# Sheet1-control.net
KiCad netlist of a schematic drawn in Altium Designer
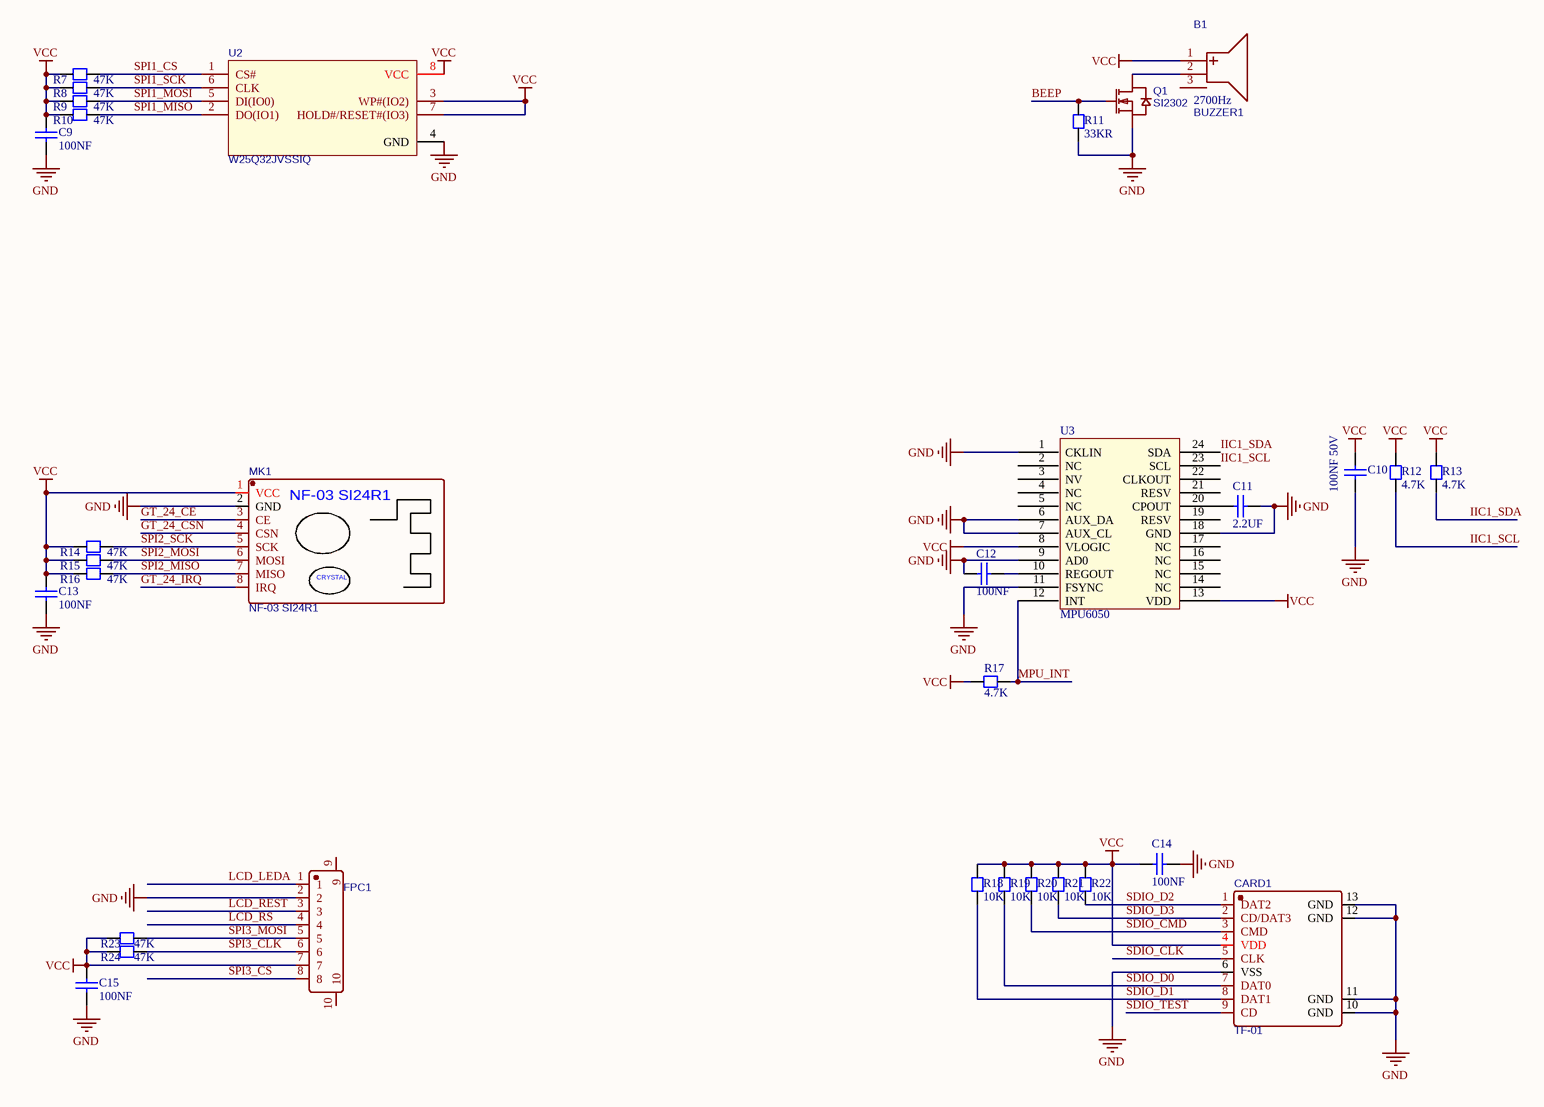
[diagram p0: Sheet1-control.SchDoc]

(export (version "E")
  (design (tool "Eeschema 10.0.6"))
  (components
    (comp (ref "B1")
      (value "BUZZER1")
      (footprint "BUZ-SMD_GSC7525RA")
      (description "2700Hz")
      (fields
        (field (name "MANUFACTURER") "INGHAi(赢海)")
        (field (name "MANUFACTURER PART") "GSC7525RA-16R2700")
        (field (name "CONTRIBUTOR") "LCSC")
      )
      (libsource (lib "base") (part "BUZZER1"))
    )
    (comp (ref "C9")
      (value "100NF")
      (footprint "CC1608-0603")
      (description "0603封装的电容")
      (fields (field (name "PUBLISHER") "Altium Limited"))
      (libsource (lib "base") (part "Cap Chip 0603"))
    )
    (comp (ref "C10")
      (value "100NF 50V")
      (footprint "CC1608-0603")
      (description "0603封装的电容")
      (fields (field (name "PUBLISHER") "Altium Limited"))
      (libsource (lib "base") (part "Cap Chip 0603"))
    )
    (comp (ref "C11")
      (value "2.2UF")
      (footprint "CC1608-0603")
      (description "0603封装的电容")
      (fields (field (name "PUBLISHER") "Altium Limited"))
      (libsource (lib "base") (part "Cap Chip 0603"))
    )
    (comp (ref "C12")
      (value "100NF")
      (footprint "CC1608-0603")
      (description "0603封装的电容")
      (fields (field (name "PUBLISHER") "Altium Limited"))
      (libsource (lib "base") (part "Cap Chip 0603"))
    )
    (comp (ref "C13")
      (value "100NF")
      (footprint "CC1608-0603")
      (description "0603封装的电容")
      (fields (field (name "PUBLISHER") "Altium Limited"))
      (libsource (lib "base") (part "Cap Chip 0603"))
    )
    (comp (ref "C14")
      (value "100NF")
      (footprint "CC1608-0603")
      (description "0603封装的电容")
      (fields (field (name "PUBLISHER") "Altium Limited"))
      (libsource (lib "base") (part "Cap Chip 0603"))
    )
    (comp (ref "C15")
      (value "100NF")
      (footprint "CC1608-0603")
      (description "0603封装的电容")
      (fields (field (name "PUBLISHER") "Altium Limited"))
      (libsource (lib "base") (part "Cap Chip 0603"))
    )
    (comp (ref "CARD1")
      (value "TF-01")
      (footprint "TF-SMD_TF-15-15")
      (fields (field (name "MANUFACTURER") "Yuandi(元迪)") (field (name "CONTRIBUTOR") "LCSC"))
      (libsource (lib "Connectors") (part "TF-01"))
    )
    (comp (ref "FPC1")
      (value "FFC 05 8P")
      (footprint "FFC-SMD_8P-P0.50")
      (fields
        (field (name "MANUFACTURER") "TXGA(特思嘉)")
        (field (name "MANUFACTURER PART") "FFC05001-08SBB124W5M-H")
        (field (name "CONTRIBUTOR") "LCSC")
      )
      (libsource (lib "Connectors") (part "FFC 05 8P"))
    )
    (comp (ref "MK1")
      (value "NF-03 SI24R1")
      (footprint "NF-03 SI24R1")
      (fields (field (name "MANUFACTURER") "Ashining(泽耀科技)") (field (name "MANUFACTURER PART") "AS01-ML01S"))
      (libsource (lib "sensor") (part "NF-03 SI24R1"))
    )
    (comp (ref "Q1")
      (value "SI2302")
      (footprint "SOT-23")
      (fields
        (field (name "MANUFACTURER") "TWGMC(台湾迪嘉)")
        (field (name "MANUFACTURER PART") "SI2306")
        (field (name "CONTRIBUTOR") "LCSC")
      )
      (libsource (lib "transistor") (part "SI2302"))
    )
    (comp (ref "R7")
      (value "47K")
      (footprint "CR1608-0603")
      (description "贴片电阻")
      (libsource (lib "tianxiaohua_Schlib") (part "Chip resistor"))
    )
    (comp (ref "R8")
      (value "47K")
      (footprint "CR1608-0603")
      (description "贴片电阻")
      (libsource (lib "tianxiaohua_Schlib") (part "Chip resistor"))
    )
    (comp (ref "R9")
      (value "47K")
      (footprint "CR1608-0603")
      (description "贴片电阻")
      (libsource (lib "tianxiaohua_Schlib") (part "Chip resistor"))
    )
    (comp (ref "R10")
      (value "47K")
      (footprint "CR1608-0603")
      (description "贴片电阻")
      (libsource (lib "tianxiaohua_Schlib") (part "Chip resistor"))
    )
    (comp (ref "R11")
      (value "33KR")
      (footprint "CR1608-0603")
      (description "贴片电阻")
      (libsource (lib "") (part "Chip resistor_1"))
    )
    (comp (ref "R12")
      (value "4.7K")
      (footprint "CR1608-0603")
      (description "0603封装电阻")
      (fields (field (name "PUBLISHER") "Altium Limited"))
      (libsource (lib "base") (part "Resistor Chip 0603"))
    )
    (comp (ref "R13")
      (value "4.7K")
      (footprint "CR1608-0603")
      (description "0603封装电阻")
      (fields (field (name "PUBLISHER") "Altium Limited"))
      (libsource (lib "base") (part "Resistor Chip 0603"))
    )
    (comp (ref "R14")
      (value "47K")
      (footprint "CR1608-0603")
      (description "0603封装电阻")
      (fields (field (name "PUBLISHER") "Altium Limited"))
      (libsource (lib "") (part "Resistor Chip 0603_2"))
    )
    (comp (ref "R15")
      (value "47K")
      (footprint "CR1608-0603")
      (description "0603封装电阻")
      (fields (field (name "PUBLISHER") "Altium Limited"))
      (libsource (lib "") (part "Resistor Chip 0603_2"))
    )
    (comp (ref "R16")
      (value "47K")
      (footprint "CR1608-0603")
      (description "0603封装电阻")
      (fields (field (name "PUBLISHER") "Altium Limited"))
      (libsource (lib "") (part "Resistor Chip 0603_2"))
    )
    (comp (ref "R17")
      (value "4.7K")
      (footprint "CR1608-0603")
      (description "0603封装电阻")
      (fields (field (name "PUBLISHER") "Altium Limited"))
      (libsource (lib "") (part "Resistor Chip 0603_2"))
    )
    (comp (ref "R18")
      (value "10K")
      (footprint "CR1608-0603")
      (description "0603封装电阻")
      (fields (field (name "PUBLISHER") "Altium Limited"))
      (libsource (lib "base") (part "Resistor Chip 0603"))
    )
    (comp (ref "R19")
      (value "10K")
      (footprint "CR1608-0603")
      (description "0603封装电阻")
      (fields (field (name "PUBLISHER") "Altium Limited"))
      (libsource (lib "base") (part "Resistor Chip 0603"))
    )
    (comp (ref "R20")
      (value "10K")
      (footprint "CR1608-0603")
      (description "0603封装电阻")
      (fields (field (name "PUBLISHER") "Altium Limited"))
      (libsource (lib "base") (part "Resistor Chip 0603"))
    )
    (comp (ref "R21")
      (value "10K")
      (footprint "CR1608-0603")
      (description "0603封装电阻")
      (fields (field (name "PUBLISHER") "Altium Limited"))
      (libsource (lib "base") (part "Resistor Chip 0603"))
    )
    (comp (ref "R22")
      (value "10K")
      (footprint "CR1608-0603")
      (description "0603封装电阻")
      (fields (field (name "PUBLISHER") "Altium Limited"))
      (libsource (lib "base") (part "Resistor Chip 0603"))
    )
    (comp (ref "R23")
      (value "47K")
      (footprint "CR1608-0603")
      (description "0603封装电阻")
      (fields (field (name "PUBLISHER") "Altium Limited"))
      (libsource (lib "") (part "Resistor Chip 0603_1"))
    )
    (comp (ref "R24")
      (value "47K")
      (footprint "CR1608-0603")
      (description "0603封装电阻")
      (fields (field (name "PUBLISHER") "Altium Limited"))
      (libsource (lib "") (part "Resistor Chip 0603_1"))
    )
    (comp (ref "U2")
      (value "W25Q32JVSSIQ")
      (footprint "SOIC-8-W25Q")
      (fields
        (field (name "MANUFACTURER") "WINBOND(华邦)")
        (field (name "MANUFACTURER PART") "W25Q128JVPIQ")
        (field (name "CONTRIBUTOR") "LCSC")
      )
      (libsource (lib "PB-Chip") (part "W25Q32JVSSIQ"))
    )
    (comp (ref "U3")
      (value "MPU6050")
      (footprint "QFN24 - duplicate")
      (description "陀螺仪")
      (libsource (lib "sensor") (part "MPU6050"))
    )
  )
  (nets
    (net (code "1") (name "/BEEP") (class "Default")
      (node (ref "Q1") (pin "1") (pinfunction "G_1") (pintype "passive"))
      (node (ref "R11") (pin "1") (pinfunction "1_1") (pintype "passive"))
    )
    (net (code "2") (name "/GT_24_CE") (class "Default")
      (node (ref "MK1") (pin "3") (pinfunction "CE_3") (pintype "passive"))
    )
    (net (code "3") (name "/GT_24_CSN") (class "Default")
      (node (ref "MK1") (pin "4") (pinfunction "CSN_4") (pintype "passive"))
    )
    (net (code "4") (name "/GT_24_IRQ") (class "Default")
      (node (ref "MK1") (pin "8") (pinfunction "IRQ_8") (pintype "passive"))
    )
    (net (code "5") (name "/IIC1_SCL") (class "Default")
      (node (ref "R12") (pin "2") (pinfunction "2_2") (pintype "passive"))
      (node (ref "U3") (pin "23") (pinfunction "SCL_23") (pintype "passive"))
    )
    (net (code "6") (name "/IIC1_SDA") (class "Default")
      (node (ref "R13") (pin "2") (pinfunction "2_2") (pintype "passive"))
      (node (ref "U3") (pin "24") (pinfunction "SDA_24") (pintype "passive"))
    )
    (net (code "7") (name "/LCD_LEDA") (class "Default")
      (node (ref "FPC1") (pin "1") (pinfunction "1_1") (pintype "passive"))
    )
    (net (code "8") (name "/LCD_REST") (class "Default")
      (node (ref "FPC1") (pin "3") (pinfunction "3_3") (pintype "passive"))
    )
    (net (code "9") (name "/LCD_RS") (class "Default")
      (node (ref "FPC1") (pin "4") (pinfunction "4_4") (pintype "passive"))
    )
    (net (code "10") (name "/MPU_INT") (class "Default")
      (node (ref "R17") (pin "2") (pinfunction "2_2") (pintype "passive"))
      (node (ref "U3") (pin "12") (pinfunction "INT_12") (pintype "passive"))
    )
    (net (code "11") (name "/SDIO_CLK") (class "Default")
      (node (ref "CARD1") (pin "5") (pinfunction "CLK_5") (pintype "passive"))
    )
    (net (code "12") (name "/SDIO_CMD") (class "Default")
      (node (ref "CARD1") (pin "3") (pinfunction "CMD_3") (pintype "passive"))
      (node (ref "R20") (pin "2") (pinfunction "2_2") (pintype "passive"))
    )
    (net (code "13") (name "/SDIO_D0") (class "Default")
      (node (ref "CARD1") (pin "7") (pinfunction "DAT0_7") (pintype "passive"))
      (node (ref "R19") (pin "2") (pinfunction "2_2") (pintype "passive"))
    )
    (net (code "14") (name "/SDIO_D1") (class "Default")
      (node (ref "CARD1") (pin "8") (pinfunction "DAT1_8") (pintype "passive"))
      (node (ref "R18") (pin "2") (pinfunction "2_2") (pintype "passive"))
    )
    (net (code "15") (name "/SDIO_D2") (class "Default")
      (node (ref "CARD1") (pin "1") (pinfunction "DAT2_1") (pintype "passive"))
      (node (ref "R22") (pin "2") (pinfunction "2_2") (pintype "passive"))
    )
    (net (code "16") (name "/SDIO_D3") (class "Default")
      (node (ref "CARD1") (pin "2") (pinfunction "CD/DAT3_2") (pintype "passive"))
      (node (ref "R21") (pin "2") (pinfunction "2_2") (pintype "passive"))
    )
    (net (code "17") (name "/SDIO_TEST") (class "Default")
      (node (ref "CARD1") (pin "9") (pinfunction "CD_9") (pintype "passive"))
    )
    (net (code "18") (name "/SPI1_CS") (class "Default")
      (node (ref "R7") (pin "2") (pinfunction "2_2") (pintype "passive"))
      (node (ref "U2") (pin "1") (pinfunction "CS#_1") (pintype "passive"))
    )
    (net (code "19") (name "/SPI1_MISO") (class "Default")
      (node (ref "R10") (pin "2") (pinfunction "2_2") (pintype "passive"))
      (node (ref "U2") (pin "2") (pinfunction "DO(IO1)_2") (pintype "passive"))
    )
    (net (code "20") (name "/SPI1_MOSI") (class "Default")
      (node (ref "R9") (pin "2") (pinfunction "2_2") (pintype "passive"))
      (node (ref "U2") (pin "5") (pinfunction "DI(IO0)_5") (pintype "passive"))
    )
    (net (code "21") (name "/SPI1_SCK") (class "Default")
      (node (ref "R8") (pin "2") (pinfunction "2_2") (pintype "passive"))
      (node (ref "U2") (pin "6") (pinfunction "CLK_6") (pintype "passive"))
    )
    (net (code "22") (name "/SPI2_MISO") (class "Default")
      (node (ref "MK1") (pin "7") (pinfunction "MISO_7") (pintype "passive"))
      (node (ref "R16") (pin "2") (pinfunction "2_2") (pintype "passive"))
    )
    (net (code "23") (name "/SPI2_MOSI") (class "Default")
      (node (ref "MK1") (pin "6") (pinfunction "MOSI_6") (pintype "passive"))
      (node (ref "R15") (pin "2") (pinfunction "2_2") (pintype "passive"))
    )
    (net (code "24") (name "/SPI2_SCK") (class "Default")
      (node (ref "MK1") (pin "5") (pinfunction "SCK_5") (pintype "passive"))
      (node (ref "R14") (pin "2") (pinfunction "2_2") (pintype "passive"))
    )
    (net (code "25") (name "/SPI3_CLK") (class "Default")
      (node (ref "FPC1") (pin "6") (pinfunction "6_6") (pintype "passive"))
      (node (ref "R24") (pin "1") (pinfunction "1_1") (pintype "passive"))
    )
    (net (code "26") (name "/SPI3_CS") (class "Default")
      (node (ref "FPC1") (pin "8") (pinfunction "8_8") (pintype "passive"))
    )
    (net (code "27") (name "/SPI3_MOSI") (class "Default")
      (node (ref "FPC1") (pin "5") (pinfunction "5_5") (pintype "passive"))
      (node (ref "R23") (pin "1") (pinfunction "1_1") (pintype "passive"))
    )
    (net (code "28") (name "GND") (class "Default")
      (node (ref "C10") (pin "1") (pinfunction "1_1") (pintype "passive"))
      (node (ref "C11") (pin "2") (pinfunction "2_2") (pintype "passive"))
      (node (ref "C12") (pin "1") (pinfunction "1_1") (pintype "passive"))
      (node (ref "C13") (pin "1") (pinfunction "1_1") (pintype "passive"))
      (node (ref "C14") (pin "1") (pinfunction "1_1") (pintype "passive"))
      (node (ref "C15") (pin "1") (pinfunction "1_1") (pintype "passive"))
      (node (ref "C9") (pin "1") (pinfunction "1_1") (pintype "passive"))
      (node (ref "CARD1") (pin "10") (pinfunction "GND_10") (pintype "passive"))
      (node (ref "CARD1") (pin "11") (pinfunction "GND_11") (pintype "passive"))
      (node (ref "CARD1") (pin "12") (pinfunction "GND_12") (pintype "passive"))
      (node (ref "CARD1") (pin "13") (pinfunction "GND_13") (pintype "passive"))
      (node (ref "CARD1") (pin "6") (pinfunction "VSS_6") (pintype "passive"))
      (node (ref "FPC1") (pin "2") (pinfunction "2_2") (pintype "passive"))
      (node (ref "MK1") (pin "2") (pinfunction "GND_2") (pintype "passive"))
      (node (ref "Q1") (pin "2") (pinfunction "S_2") (pintype "passive"))
      (node (ref "R11") (pin "2") (pinfunction "2_2") (pintype "passive"))
      (node (ref "U2") (pin "4") (pinfunction "GND_4") (pintype "passive"))
      (node (ref "U3") (pin "1") (pinfunction "CKLIN_1") (pintype "passive"))
      (node (ref "U3") (pin "11") (pinfunction "FSYNC_11") (pintype "passive"))
      (node (ref "U3") (pin "18") (pinfunction "GND_18") (pintype "passive"))
      (node (ref "U3") (pin "6") (pinfunction "AUX_DA_6") (pintype "passive"))
      (node (ref "U3") (pin "7") (pinfunction "AUX_CL_7") (pintype "passive"))
      (node (ref "U3") (pin "9") (pinfunction "AD0_9") (pintype "passive"))
    )
    (net (code "29") (name "Net-(B1--)") (class "Default")
      (node (ref "B1") (pin "2") (pinfunction "-_2") (pintype "passive"))
      (node (ref "Q1") (pin "3") (pinfunction "D_3") (pintype "passive"))
    )
    (net (code "30") (name "Net-(U3-CPOUT)") (class "Default")
      (node (ref "C11") (pin "1") (pinfunction "1_1") (pintype "passive"))
      (node (ref "U3") (pin "20") (pinfunction "CPOUT_20") (pintype "passive"))
    )
    (net (code "31") (name "Net-(U3-REGOUT)") (class "Default")
      (node (ref "C12") (pin "2") (pinfunction "2_2") (pintype "passive"))
      (node (ref "U3") (pin "10") (pinfunction "REGOUT_10") (pintype "passive"))
    )
    (net (code "32") (name "VCC") (class "Default")
      (node (ref "B1") (pin "1") (pinfunction "+_1") (pintype "passive"))
      (node (ref "C10") (pin "2") (pinfunction "2_2") (pintype "passive"))
      (node (ref "C13") (pin "2") (pinfunction "2_2") (pintype "passive"))
      (node (ref "C14") (pin "2") (pinfunction "2_2") (pintype "passive"))
      (node (ref "C15") (pin "2") (pinfunction "2_2") (pintype "passive"))
      (node (ref "C9") (pin "2") (pinfunction "2_2") (pintype "passive"))
      (node (ref "CARD1") (pin "4") (pinfunction "VDD_4") (pintype "passive"))
      (node (ref "FPC1") (pin "7") (pinfunction "7_7") (pintype "passive"))
      (node (ref "MK1") (pin "1") (pinfunction "VCC_1") (pintype "passive"))
      (node (ref "R10") (pin "1") (pinfunction "1_1") (pintype "passive"))
      (node (ref "R12") (pin "1") (pinfunction "1_1") (pintype "passive"))
      (node (ref "R13") (pin "1") (pinfunction "1_1") (pintype "passive"))
      (node (ref "R14") (pin "1") (pinfunction "1_1") (pintype "passive"))
      (node (ref "R15") (pin "1") (pinfunction "1_1") (pintype "passive"))
      (node (ref "R16") (pin "1") (pinfunction "1_1") (pintype "passive"))
      (node (ref "R17") (pin "1") (pinfunction "1_1") (pintype "passive"))
      (node (ref "R18") (pin "1") (pinfunction "1_1") (pintype "passive"))
      (node (ref "R19") (pin "1") (pinfunction "1_1") (pintype "passive"))
      (node (ref "R20") (pin "1") (pinfunction "1_1") (pintype "passive"))
      (node (ref "R21") (pin "1") (pinfunction "1_1") (pintype "passive"))
      (node (ref "R22") (pin "1") (pinfunction "1_1") (pintype "passive"))
      (node (ref "R23") (pin "2") (pinfunction "2_2") (pintype "passive"))
      (node (ref "R24") (pin "2") (pinfunction "2_2") (pintype "passive"))
      (node (ref "R7") (pin "1") (pinfunction "1_1") (pintype "passive"))
      (node (ref "R8") (pin "1") (pinfunction "1_1") (pintype "passive"))
      (node (ref "R9") (pin "1") (pinfunction "1_1") (pintype "passive"))
      (node (ref "U2") (pin "3") (pinfunction "WP#(IO2)_3") (pintype "passive"))
      (node (ref "U2") (pin "7") (pinfunction "HOLD#/RESET#(IO3)_7") (pintype "passive"))
      (node (ref "U2") (pin "8") (pinfunction "VCC_8") (pintype "passive"))
      (node (ref "U3") (pin "13") (pinfunction "VDD_13") (pintype "passive"))
      (node (ref "U3") (pin "8") (pinfunction "VLOGIC_8") (pintype "passive"))
    )
    (net (code "33") (name "unconnected-(B1-EH-Pad3)") (class "Default")
      (node (ref "B1") (pin "3") (pinfunction "EH_3") (pintype "passive"))
    )
    (net (code "34") (name "unconnected-(FPC1-Pad9)") (class "Default")
      (node (ref "FPC1") (pin "9") (pinfunction "9_9") (pintype "passive"))
    )
    (net (code "35") (name "unconnected-(FPC1-Pad10)") (class "Default")
      (node (ref "FPC1") (pin "10") (pinfunction "10_10") (pintype "passive"))
    )
    (net (code "36") (name "unconnected-(U3-CLKOUT-Pad22)") (class "Default")
      (node (ref "U3") (pin "22") (pinfunction "CLKOUT_22") (pintype "passive"))
    )
    (net (code "37") (name "unconnected-(U3-NC-Pad2)") (class "Default")
      (node (ref "U3") (pin "2") (pinfunction "NC_2") (pintype "passive"))
    )
    (net (code "38") (name "unconnected-(U3-NC-Pad4)") (class "Default")
      (node (ref "U3") (pin "4") (pinfunction "NC_4") (pintype "passive"))
    )
    (net (code "39") (name "unconnected-(U3-NC-Pad5)") (class "Default")
      (node (ref "U3") (pin "5") (pinfunction "NC_5") (pintype "passive"))
    )
    (net (code "40") (name "unconnected-(U3-NC-Pad14)") (class "Default")
      (node (ref "U3") (pin "14") (pinfunction "NC_14") (pintype "passive"))
    )
    (net (code "41") (name "unconnected-(U3-NC-Pad15)") (class "Default")
      (node (ref "U3") (pin "15") (pinfunction "NC_15") (pintype "passive"))
    )
    (net (code "42") (name "unconnected-(U3-NC-Pad16)") (class "Default")
      (node (ref "U3") (pin "16") (pinfunction "NC_16") (pintype "passive"))
    )
    (net (code "43") (name "unconnected-(U3-NC-Pad17)") (class "Default")
      (node (ref "U3") (pin "17") (pinfunction "NC_17") (pintype "passive"))
    )
    (net (code "44") (name "unconnected-(U3-NV-Pad3)") (class "Default")
      (node (ref "U3") (pin "3") (pinfunction "NV_3") (pintype "passive"))
    )
    (net (code "45") (name "unconnected-(U3-RESV-Pad19)") (class "Default")
      (node (ref "U3") (pin "19") (pinfunction "RESV_19") (pintype "passive"))
    )
    (net (code "46") (name "unconnected-(U3-RESV-Pad21)") (class "Default")
      (node (ref "U3") (pin "21") (pinfunction "RESV_21") (pintype "passive"))
    )
  )
)
